# 001-H-01_CAN_to_Bluetooth.net
KiCad netlist of a schematic drawn in Altium Designer
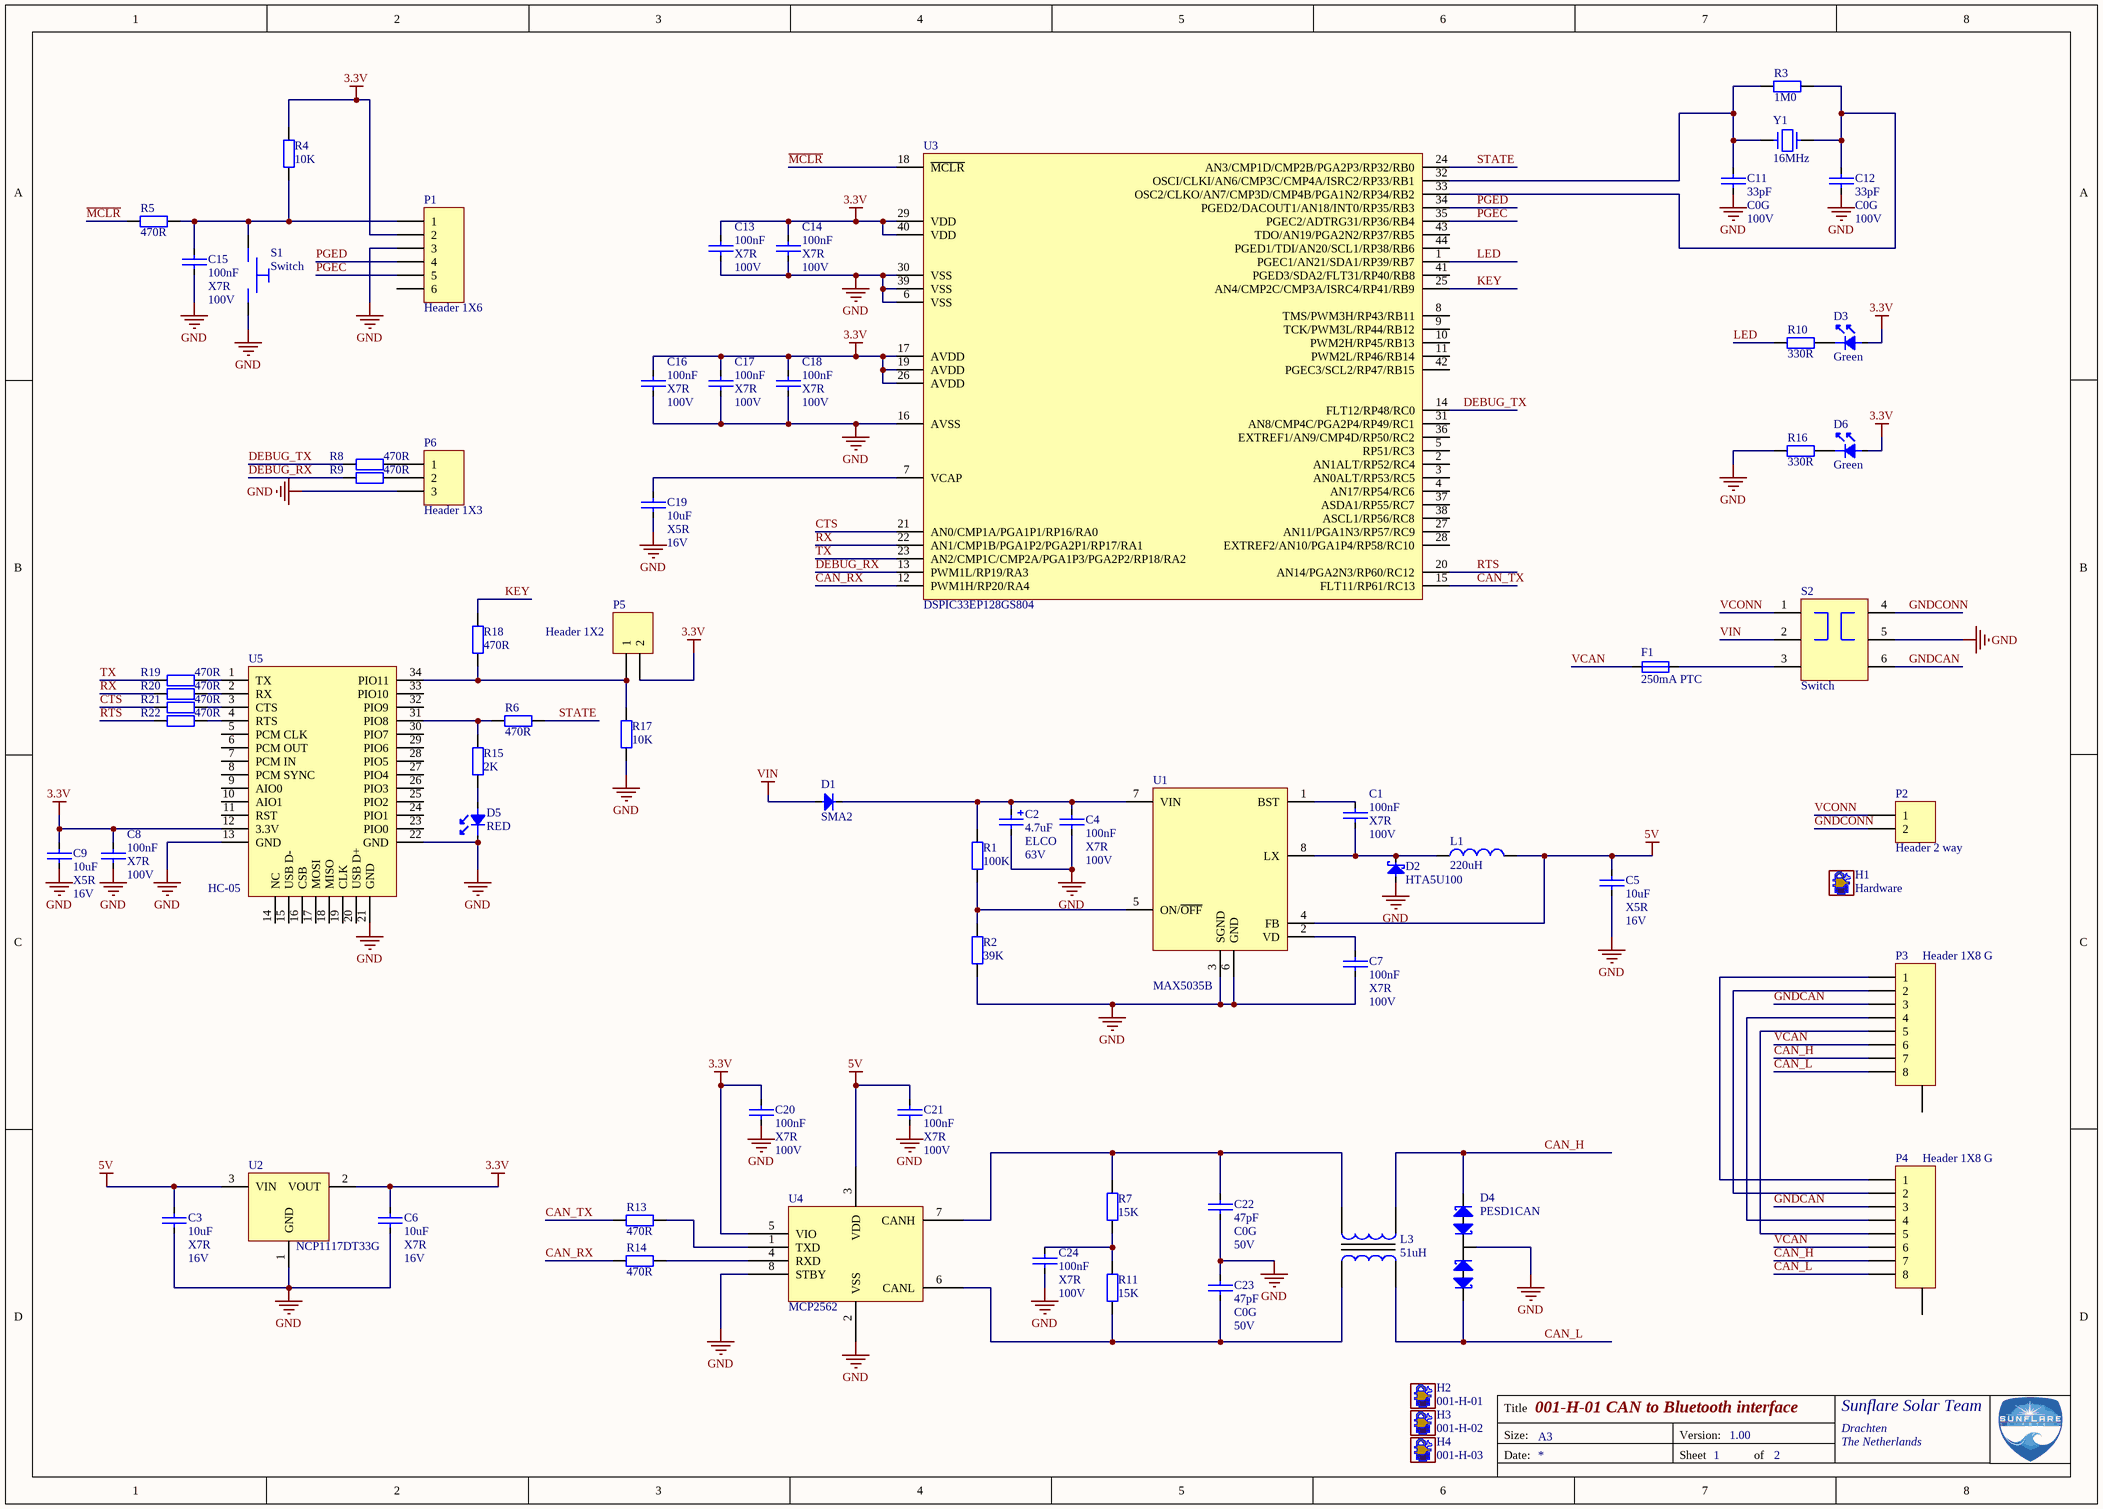
[diagram p0: 001-H-01 CAN to Bluetooth.SchDoc]

(export (version "E")
  (design (tool "Eeschema 10.0.6"))
  (components
    (comp (ref "C1")
      (value "100nF")
      (footprint "CAP0805")
      (description "Capacitor")
      (fields (field (name "DIELECTRIC") "X7R") (field (name "VOLTAGERATING") "100V"))
      (libsource (lib "001-H-01 CAN to Bluetooth") (part "Capacitor"))
    )
    (comp (ref "C2")
      (value "4.7uF")
      (footprint "CAPPOL5MM")
      (description "Capacitor Pol")
      (fields
        (field (name "MANUFACTURER") "WURTH ELEKTRONIK")
        (field (name "MANUFACTURER PART NO") "865060742001")
        (field (name "DIELECTRIC") "ELCO")
        (field (name "VOLTAGERATING") "63V")
      )
      (libsource (lib "001-H-01 CAN to Bluetooth") (part "CapacitorPol"))
    )
    (comp (ref "C3")
      (value "10uF")
      (footprint "CAP1210")
      (description "Capacitor")
      (fields
        (field (name "MANUFACTURER") "TDK")
        (field (name "MANUFACTURER PART NO") "C3225X7R1C106K200AB")
        (field (name "DIELECTRIC") "X7R")
        (field (name "VOLTAGERATING") "16V")
      )
      (libsource (lib "001-H-01 CAN to Bluetooth") (part "Capacitor"))
    )
    (comp (ref "C4")
      (value "100nF")
      (footprint "CAP0805")
      (description "Capacitor")
      (fields (field (name "DIELECTRIC") "X7R") (field (name "VOLTAGERATING") "100V"))
      (libsource (lib "001-H-01 CAN to Bluetooth") (part "Capacitor"))
    )
    (comp (ref "C5")
      (value "10uF")
      (footprint "CAP1210")
      (description "Capacitor")
      (fields
        (field (name "MANUFACTURER") "Multicomp")
        (field (name "MANUFACTURER PART NO") "MC1210X106K160CT")
        (field (name "DIELECTRIC") "X5R")
        (field (name "VOLTAGERATING") "16V")
      )
      (libsource (lib "001-H-01 CAN to Bluetooth") (part "Capacitor"))
    )
    (comp (ref "C6")
      (value "10uF")
      (footprint "CAP1210")
      (description "Capacitor")
      (fields
        (field (name "MANUFACTURER") "TDK")
        (field (name "MANUFACTURER PART NO") "C3225X7R1C106K200AB")
        (field (name "DIELECTRIC") "X7R")
        (field (name "VOLTAGERATING") "16V")
      )
      (libsource (lib "001-H-01 CAN to Bluetooth") (part "Capacitor"))
    )
    (comp (ref "C7")
      (value "100nF")
      (footprint "CAP0805")
      (description "Capacitor")
      (fields (field (name "DIELECTRIC") "X7R") (field (name "VOLTAGERATING") "100V"))
      (libsource (lib "001-H-01 CAN to Bluetooth") (part "Capacitor"))
    )
    (comp (ref "C8")
      (value "100nF")
      (footprint "CAP0805")
      (description "Capacitor")
      (fields (field (name "DIELECTRIC") "X7R") (field (name "VOLTAGERATING") "100V"))
      (libsource (lib "001-H-01 CAN to Bluetooth") (part "Capacitor"))
    )
    (comp (ref "C9")
      (value "10uF")
      (footprint "CAP1210")
      (description "Capacitor")
      (fields
        (field (name "MANUFACTURER") "Multicomp")
        (field (name "MANUFACTURER PART NO") "MC1210X106K160CT")
        (field (name "DIELECTRIC") "X5R")
        (field (name "VOLTAGERATING") "16V")
      )
      (libsource (lib "001-H-01 CAN to Bluetooth") (part "Capacitor"))
    )
    (comp (ref "C11")
      (value "33pF")
      (footprint "CAP0805")
      (description "Capacitor")
      (fields (field (name "DIELECTRIC") "C0G") (field (name "VOLTAGERATING") "100V"))
      (libsource (lib "001-H-01 CAN to Bluetooth") (part "Capacitor"))
    )
    (comp (ref "C12")
      (value "33pF")
      (footprint "CAP0805")
      (description "Capacitor")
      (fields (field (name "DIELECTRIC") "C0G") (field (name "VOLTAGERATING") "100V"))
      (libsource (lib "001-H-01 CAN to Bluetooth") (part "Capacitor"))
    )
    (comp (ref "C13")
      (value "100nF")
      (footprint "CAP0805")
      (description "Capacitor")
      (fields (field (name "DIELECTRIC") "X7R") (field (name "VOLTAGERATING") "100V"))
      (libsource (lib "001-H-01 CAN to Bluetooth") (part "Capacitor"))
    )
    (comp (ref "C14")
      (value "100nF")
      (footprint "CAP0805")
      (description "Capacitor")
      (fields (field (name "DIELECTRIC") "X7R") (field (name "VOLTAGERATING") "100V"))
      (libsource (lib "001-H-01 CAN to Bluetooth") (part "Capacitor"))
    )
    (comp (ref "C15")
      (value "100nF")
      (footprint "CAP0805")
      (description "Capacitor")
      (fields (field (name "DIELECTRIC") "X7R") (field (name "VOLTAGERATING") "100V"))
      (libsource (lib "001-H-01 CAN to Bluetooth") (part "Capacitor"))
    )
    (comp (ref "C16")
      (value "100nF")
      (footprint "CAP0805")
      (description "Capacitor")
      (fields (field (name "DIELECTRIC") "X7R") (field (name "VOLTAGERATING") "100V"))
      (libsource (lib "001-H-01 CAN to Bluetooth") (part "Capacitor"))
    )
    (comp (ref "C17")
      (value "100nF")
      (footprint "CAP0805")
      (description "Capacitor")
      (fields (field (name "DIELECTRIC") "X7R") (field (name "VOLTAGERATING") "100V"))
      (libsource (lib "001-H-01 CAN to Bluetooth") (part "Capacitor"))
    )
    (comp (ref "C18")
      (value "100nF")
      (footprint "CAP0805")
      (description "Capacitor")
      (fields (field (name "DIELECTRIC") "X7R") (field (name "VOLTAGERATING") "100V"))
      (libsource (lib "001-H-01 CAN to Bluetooth") (part "Capacitor"))
    )
    (comp (ref "C19")
      (value "10uF")
      (footprint "CAP1210")
      (description "Capacitor")
      (fields
        (field (name "MANUFACTURER") "Multicomp")
        (field (name "MANUFACTURER PART NO") "MC1210X106K160CT")
        (field (name "DIELECTRIC") "X5R")
        (field (name "VOLTAGERATING") "16V")
      )
      (libsource (lib "001-H-01 CAN to Bluetooth") (part "Capacitor"))
    )
    (comp (ref "C20")
      (value "100nF")
      (footprint "CAP0805")
      (description "Capacitor")
      (fields (field (name "DIELECTRIC") "X7R") (field (name "VOLTAGERATING") "100V"))
      (libsource (lib "001-H-01 CAN to Bluetooth") (part "Capacitor"))
    )
    (comp (ref "C21")
      (value "100nF")
      (footprint "CAP0805")
      (description "Capacitor")
      (fields (field (name "DIELECTRIC") "X7R") (field (name "VOLTAGERATING") "100V"))
      (libsource (lib "001-H-01 CAN to Bluetooth") (part "Capacitor"))
    )
    (comp (ref "C22")
      (value "47pF")
      (footprint "CAP0805")
      (description "Capacitor")
      (fields (field (name "DIELECTRIC") "C0G") (field (name "VOLTAGERATING") "50V"))
      (libsource (lib "001-H-01 CAN to Bluetooth") (part "Capacitor"))
    )
    (comp (ref "C23")
      (value "47pF")
      (footprint "CAP0805")
      (description "Capacitor")
      (fields (field (name "DIELECTRIC") "C0G") (field (name "VOLTAGERATING") "50V"))
      (libsource (lib "001-H-01 CAN to Bluetooth") (part "Capacitor"))
    )
    (comp (ref "C24")
      (value "100nF")
      (footprint "CAP0805")
      (description "Capacitor")
      (fields (field (name "DIELECTRIC") "X7R") (field (name "VOLTAGERATING") "100V"))
      (libsource (lib "001-H-01 CAN to Bluetooth") (part "Capacitor"))
    )
    (comp (ref "D1")
      (value "SMA2")
      (footprint "DIODEDO-214AC")
      (description "Diode")
      (fields (field (name "MANUFACTURER") "Multicomp") (field (name "MANUFACTURER PART NO") "S2MA"))
      (libsource (lib "001-H-01 CAN to Bluetooth") (part "Diode"))
    )
    (comp (ref "D2")
      (value "HTA5U100")
      (footprint "DIODEDO-214AC")
      (description "Diode Schottky")
      (fields (field (name "MANUFACTURER") "Multicomp"))
      (libsource (lib "001-H-01 CAN to Bluetooth") (part "Diode Schottky"))
    )
    (comp (ref "D3")
      (value "Green")
      (footprint "LEDTHT")
      (description "Led")
      (fields (field (name "MANUFACTURER") "Multicomp") (field (name "MANUFACTURER PART NO") "MCL034GT"))
      (libsource (lib "001-H-01 CAN to Bluetooth") (part "Led"))
    )
    (comp (ref "D4")
      (value "PESD1CAN")
      (footprint "SOT23-3N")
      (description "ESD Protection Device, TVS, 70 V, SOT-23, 3 Pins")
      (fields (field (name "MANUFACTURER") "NXP"))
      (libsource (lib "001-H-01 CAN to Bluetooth") (part "PESD1CAN"))
    )
    (comp (ref "D5")
      (value "RED")
      (footprint "LEDTHT")
      (description "Led")
      (fields (field (name "MANUFACTURER") "Multicomp") (field (name "MANUFACTURER PART NO") "MCL034PT"))
      (libsource (lib "001-H-01 CAN to Bluetooth") (part "Led"))
    )
    (comp (ref "D6")
      (value "Green")
      (footprint "LEDTHT")
      (description "Led")
      (fields (field (name "MANUFACTURER") "Multicomp") (field (name "MANUFACTURER PART NO") "MCL034GT"))
      (libsource (lib "001-H-01 CAN to Bluetooth") (part "Led"))
    )
    (comp (ref "F1")
      (value "250mA PTC")
      (footprint "Fuse 1206")
      (description "Fuse")
      (fields
        (field (name "MANUFACTURER") "EATON BUSSMANN SERIES")
        (field (name "MANUFACTURER PART NO") "PTS120660V010")
      )
      (libsource (lib "001-H-01 CAN to Bluetooth") (part "Fuse"))
    )
    (comp (ref "H1")
      (value "Hardware")
      (description "Generaric hardware")
      (fields
        (field (name "MANUFACTURER") "IMO PRECISION CONTROLS")
        (field (name "MANUFACTURER PART NO") "21.950M/2-E")
      )
      (libsource (lib "001-H-01 CAN to Bluetooth") (part "Hardware"))
    )
    (comp (ref "H2")
      (value "001-H-01")
      (description "PCB")
      (libsource (lib "001-H-01 CAN to Bluetooth") (part "Hardware"))
    )
    (comp (ref "H3")
      (value "001-H-02")
      (description "Casing bottom")
      (libsource (lib "001-H-01 CAN to Bluetooth") (part "Hardware"))
    )
    (comp (ref "H4")
      (value "001-H-03")
      (description "Casing top")
      (libsource (lib "001-H-01 CAN to Bluetooth") (part "Hardware"))
    )
    (comp (ref "L1")
      (value "220uH")
      (footprint "INDWE-PD")
      (description "Inductor")
      (fields (field (name "MANUFACTURER") "WE") (field (name "MANUFACTURER PART NO") "744777222"))
      (libsource (lib "001-H-01 CAN to Bluetooth") (part "Inductor"))
    )
    (comp (ref "L3")
      (value "51uH")
      (footprint "IND200P450X300-4N")
      (description "Choke common mode")
      (fields (field (name "MANUFACTURER") "Bourns") (field (name "MANUFACTURER PART NO") "SRF4532-510Y"))
      (libsource (lib "001-H-01 CAN to Bluetooth") (part "Choke Common Mode"))
    )
    (comp (ref "P1")
      (value "Header 1X6")
      (footprint "Header1X6P100_Program")
      (description "Connector 1X6")
      (libsource (lib "001-H-01 CAN to Bluetooth") (part "Header1X6"))
    )
    (comp (ref "P2")
      (value "Header 2 way")
      (footprint "21.95MH/2-E")
      (fields
        (field (name "MANUFACTURER") "IMO PRECISION CONTROLS")
        (field (name "MANUFACTURER PART NO") "21.95MH/2-E")
      )
      (libsource (lib "") (part "Header1X2_1"))
    )
    (comp (ref "P3")
      (value "Header 1X8 G")
      (footprint "TECO-1-406541-5")
      (description "Connector 1X8 with Ground")
      (libsource (lib "001-H-01 CAN to Bluetooth") (part "Header1X8+G"))
    )
    (comp (ref "P4")
      (value "Header 1X8 G")
      (footprint "TECO-1-406541-5")
      (description "Connector 1X8 with Ground")
      (libsource (lib "001-H-01 CAN to Bluetooth") (part "Header1X8+G"))
    )
    (comp (ref "P5")
      (value "Header 1X2")
      (footprint "Header1X2P100")
      (description "Connector 1X2")
      (libsource (lib "001-H-01 CAN to Bluetooth") (part "Header1X2"))
    )
    (comp (ref "P6")
      (value "Header 1X3")
      (footprint "Header1X3P100")
      (description "Connector 1X3")
      (libsource (lib "001-H-01 CAN to Bluetooth") (part "Header1X3"))
    )
    (comp (ref "R1")
      (value "100K")
      (footprint "RES0603")
      (description "Resistor")
      (fields (field (name "TOLERANCE") "1%"))
      (libsource (lib "") (part "Resistor_2"))
    )
    (comp (ref "R2")
      (value "39K")
      (footprint "RES0603")
      (description "Resistor")
      (fields (field (name "TOLERANCE") "1%"))
      (libsource (lib "") (part "Resistor_2"))
    )
    (comp (ref "R3")
      (value "1M0")
      (footprint "RES0603")
      (description "Resistor")
      (fields (field (name "TOLERANCE") "1%"))
      (libsource (lib "") (part "Resistor_1"))
    )
    (comp (ref "R4")
      (value "10K")
      (footprint "RES0603")
      (description "Resistor")
      (fields (field (name "TOLERANCE") "1%"))
      (libsource (lib "") (part "Resistor_2"))
    )
    (comp (ref "R5")
      (value "470R")
      (footprint "RES0603")
      (description "Resistor")
      (fields (field (name "TOLERANCE") "1%"))
      (libsource (lib "") (part "Resistor_1"))
    )
    (comp (ref "R6")
      (value "470R")
      (footprint "RES0603")
      (description "Resistor")
      (fields (field (name "TOLERANCE") "1%"))
      (libsource (lib "") (part "Resistor_1"))
    )
    (comp (ref "R7")
      (value "15K")
      (footprint "RES0603")
      (description "Resistor")
      (fields (field (name "TOLERANCE") "1%"))
      (libsource (lib "") (part "Resistor_2"))
    )
    (comp (ref "R8")
      (value "470R")
      (footprint "RES0603")
      (description "Resistor")
      (fields (field (name "TOLERANCE") "1%"))
      (libsource (lib "") (part "Resistor_1"))
    )
    (comp (ref "R9")
      (value "470R")
      (footprint "RES0603")
      (description "Resistor")
      (fields (field (name "TOLERANCE") "1%"))
      (libsource (lib "") (part "Resistor_1"))
    )
    (comp (ref "R10")
      (value "330R")
      (footprint "RES0603")
      (description "Resistor")
      (fields (field (name "TOLERANCE") "1%"))
      (libsource (lib "") (part "Resistor_1"))
    )
    (comp (ref "R11")
      (value "15K")
      (footprint "RES0603")
      (description "Resistor")
      (fields (field (name "TOLERANCE") "1%"))
      (libsource (lib "") (part "Resistor_2"))
    )
    (comp (ref "R13")
      (value "470R")
      (footprint "RES0603")
      (description "Resistor")
      (fields (field (name "TOLERANCE") "1%"))
      (libsource (lib "") (part "Resistor_1"))
    )
    (comp (ref "R14")
      (value "470R")
      (footprint "RES0603")
      (description "Resistor")
      (fields (field (name "TOLERANCE") "1%"))
      (libsource (lib "") (part "Resistor_1"))
    )
    (comp (ref "R15")
      (value "2K")
      (footprint "RES0603")
      (description "Resistor")
      (fields (field (name "TOLERANCE") "1%"))
      (libsource (lib "") (part "Resistor_2"))
    )
    (comp (ref "R16")
      (value "330R")
      (footprint "RES0603")
      (description "Resistor")
      (fields (field (name "TOLERANCE") "1%"))
      (libsource (lib "") (part "Resistor_1"))
    )
    (comp (ref "R17")
      (value "10K")
      (footprint "RES0603")
      (description "Resistor")
      (fields (field (name "TOLERANCE") "1%"))
      (libsource (lib "001-H-01 CAN to Bluetooth") (part "Resistor"))
    )
    (comp (ref "R18")
      (value "470R")
      (footprint "RES0603")
      (description "Resistor")
      (fields (field (name "TOLERANCE") "1%"))
      (libsource (lib "001-H-01 CAN to Bluetooth") (part "Resistor"))
    )
    (comp (ref "R19")
      (value "470R")
      (footprint "RES0603")
      (description "Resistor")
      (fields (field (name "TOLERANCE") "1%"))
      (libsource (lib "") (part "Resistor_1"))
    )
    (comp (ref "R20")
      (value "470R")
      (footprint "RES0603")
      (description "Resistor")
      (fields (field (name "TOLERANCE") "1%"))
      (libsource (lib "") (part "Resistor_1"))
    )
    (comp (ref "R21")
      (value "470R")
      (footprint "RES0603")
      (description "Resistor")
      (fields (field (name "TOLERANCE") "1%"))
      (libsource (lib "") (part "Resistor_1"))
    )
    (comp (ref "R22")
      (value "470R")
      (footprint "RES0603")
      (description "Resistor")
      (fields (field (name "TOLERANCE") "1%"))
      (libsource (lib "") (part "Resistor_1"))
    )
    (comp (ref "S1")
      (value "Switch")
      (footprint "SWITCHTE1825027-2")
      (description "Tactile Switch")
      (fields
        (field (name "MANUFACTURER") "TE CONNECTIVITY")
        (field (name "MANUFACTURER PART NO") "FSMRA4JH")
      )
      (libsource (lib "001-H-01 CAN to Bluetooth") (part "TactileSwitch"))
    )
    (comp (ref "S2")
      (value "Switch")
      (footprint "JS202011AQN")
      (description "Tactile Switch")
      (fields
        (field (name "MANUFACTURER") "C&K COMPONENTS")
        (field (name "MANUFACTURER PART NO") "JS202011AQN")
      )
      (libsource (lib "001-H-01 CAN to Bluetooth") (part "DPDTSwitch"))
    )
    (comp (ref "U1")
      (value "MAX5035B")
      (footprint "SOIC-8N")
      (description "5V 1A, 76V, High-Efficiency MAXPower Step-Down DC-DC Converter")
      (fields
        (field (name "MANUFACTURER") "Maxim Integrated Products")
        (field (name "MANUFACTURER PART NO") "MAX5035BUSA+T")
      )
      (libsource (lib "001-H-01 CAN to Bluetooth") (part "MAX5035B"))
    )
    (comp (ref "U2")
      (value "NCP1117DT33G")
      (footprint "DPAK-3")
      (description "Fixed LDO Voltage Regulator, 20V in, 1.07V Dropout, 3.3V/1A out, DPAK-3")
      (fields (field (name "MANUFACTURER") "ON SEMICONDUCTOR"))
      (libsource (lib "001-H-01 CAN to Bluetooth") (part "NCP1117DT33G"))
    )
    (comp (ref "U3")
      (value "DSPIC33EP128GS804")
      (footprint "TQFP80P1200X1200X120-44N")
      (fields
        (field (name "MANUFACTURER") "Microchip")
        (field (name "MANUFACTURER PART NO") "DSPIC33EP128GS804-I/PT")
      )
      (libsource (lib "001-H-01 CAN to Bluetooth") (part "DSPIC33EP128GS804"))
    )
    (comp (ref "U4")
      (value "MCP2562")
      (footprint "SOIC-8N")
      (description "CAN Bus, Transceiver, CAN, LIN, 1, 1, 4.5 V, 5.5 V, SOIC")
      (fields (field (name "MANUFACTURER") "Microchip") (field (name "MANUFACTURER PART NO") "MCP2562-E/SN"))
      (libsource (lib "001-H-01 CAN to Bluetooth") (part "MCP2562"))
    )
    (comp (ref "U5")
      (value "HC-05")
      (footprint "HC-05")
      (description "Bluetooth Module")
      (libsource (lib "001-H-01 CAN to Bluetooth") (part "HC-05"))
    )
    (comp (ref "Y1")
      (value "16MHz")
      (footprint "XT49M-2016M")
      (description "Crystal")
      (fields
        (field (name "MANUFACTURER") "Multicomp")
        (field (name "MANUFACTURER PART NO") "MCRSD16000F183000RR")
      )
      (libsource (lib "001-H-01 CAN to Bluetooth") (part "Crystal"))
    )
  )
  (nets
    (net (code "1") (name "/CAN_H") (class "Default")
      (node (ref "D4") (pin "1") (pinfunction "1_1") (pintype "passive"))
      (node (ref "L3") (pin "2") (pinfunction "2_2") (pintype "passive"))
      (node (ref "P3") (pin "7") (pinfunction "7_7") (pintype "passive"))
      (node (ref "P4") (pin "7") (pinfunction "7_7") (pintype "passive"))
    )
    (net (code "2") (name "/CAN_L") (class "Default")
      (node (ref "D4") (pin "2") (pinfunction "2_2") (pintype "passive"))
      (node (ref "L3") (pin "3") (pinfunction "3_3") (pintype "passive"))
      (node (ref "P3") (pin "8") (pinfunction "8_8") (pintype "passive"))
      (node (ref "P4") (pin "8") (pinfunction "8_8") (pintype "passive"))
    )
    (net (code "3") (name "/CAN_RX") (class "Default")
      (node (ref "R14") (pin "1") (pinfunction "1_1") (pintype "passive"))
      (node (ref "U3") (pin "12") (pinfunction "PWM1H/RP20/RA4_12") (pintype "passive"))
    )
    (net (code "4") (name "/CAN_TX") (class "Default")
      (node (ref "R13") (pin "1") (pinfunction "1_1") (pintype "passive"))
      (node (ref "U3") (pin "15") (pinfunction "FLT11/RP61/RC13_15") (pintype "passive"))
    )
    (net (code "5") (name "/CTS") (class "Default")
      (node (ref "R21") (pin "1") (pinfunction "1_1") (pintype "passive"))
      (node (ref "U3") (pin "21") (pinfunction "AN0/CMP1A/PGA1P1/RP16/RA0_21") (pintype "passive"))
    )
    (net (code "6") (name "/DEBUG_RX") (class "Default")
      (node (ref "R9") (pin "1") (pinfunction "1_1") (pintype "passive"))
      (node (ref "U3") (pin "13") (pinfunction "PWM1L/RP19/RA3_13") (pintype "passive"))
    )
    (net (code "7") (name "/DEBUG_TX") (class "Default")
      (node (ref "R8") (pin "1") (pinfunction "1_1") (pintype "passive"))
      (node (ref "U3") (pin "14") (pinfunction "FLT12/RP48/RC0_14") (pintype "passive"))
    )
    (net (code "8") (name "/GNDCAN") (class "Default")
      (node (ref "P3") (pin "3") (pinfunction "3_3") (pintype "passive"))
      (node (ref "P4") (pin "3") (pinfunction "3_3") (pintype "passive"))
      (node (ref "S2") (pin "6") (pinfunction "6_6") (pintype "passive"))
    )
    (net (code "9") (name "/GNDCONN") (class "Default")
      (node (ref "P2") (pin "2") (pinfunction "2_2") (pintype "passive"))
      (node (ref "S2") (pin "4") (pinfunction "4_4") (pintype "passive"))
    )
    (net (code "10") (name "/KEY") (class "Default")
      (node (ref "R18") (pin "2") (pinfunction "2_2") (pintype "passive"))
      (node (ref "U3") (pin "25") (pinfunction "AN4/CMP2C/CMP3A/ISRC4/RP41/RB9_25") (pintype "passive"))
    )
    (net (code "11") (name "/LED") (class "Default")
      (node (ref "R10") (pin "1") (pinfunction "1_1") (pintype "passive"))
      (node (ref "U3") (pin "1") (pinfunction "PGEC1/AN21/SDA1/RP39/RB7_1") (pintype "passive"))
    )
    (net (code "12") (name "/PGEC") (class "Default")
      (node (ref "P1") (pin "5") (pinfunction "5_5") (pintype "passive"))
      (node (ref "U3") (pin "35") (pinfunction "PGEC2/ADTRG31/RP36/RB4_35") (pintype "passive"))
    )
    (net (code "13") (name "/PGED") (class "Default")
      (node (ref "P1") (pin "4") (pinfunction "4_4") (pintype "passive"))
      (node (ref "U3") (pin "34") (pinfunction "PGED2/DACOUT1/AN18/INT0/RP35/RB3_34") (pintype "passive"))
    )
    (net (code "14") (name "/RTS") (class "Default")
      (node (ref "R22") (pin "1") (pinfunction "1_1") (pintype "passive"))
      (node (ref "U3") (pin "20") (pinfunction "AN14/PGA2N3/RP60/RC12_20") (pintype "passive"))
    )
    (net (code "15") (name "/RX") (class "Default")
      (node (ref "R20") (pin "1") (pinfunction "1_1") (pintype "passive"))
      (node (ref "U3") (pin "22") (pinfunction "AN1/CMP1B/PGA1P2/PGA2P1/RP17/RA1_22") (pintype "passive"))
    )
    (net (code "16") (name "/STATE") (class "Default")
      (node (ref "R6") (pin "2") (pinfunction "2_2") (pintype "passive"))
      (node (ref "U3") (pin "24") (pinfunction "AN3/CMP1D/CMP2B/PGA2P3/RP32/RB0_24") (pintype "passive"))
    )
    (net (code "17") (name "/TX") (class "Default")
      (node (ref "R19") (pin "1") (pinfunction "1_1") (pintype "passive"))
      (node (ref "U3") (pin "23") (pinfunction "AN2/CMP1C/CMP2A/PGA1P3/PGA2P2/RP18/RA2_23") (pintype "passive"))
    )
    (net (code "18") (name "/VCAN") (class "Default")
      (node (ref "F1") (pin "1") (pinfunction "1_1") (pintype "passive"))
      (node (ref "P3") (pin "6") (pinfunction "6_6") (pintype "passive"))
      (node (ref "P4") (pin "6") (pinfunction "6_6") (pintype "passive"))
    )
    (net (code "19") (name "/VCONN") (class "Default")
      (node (ref "P2") (pin "1") (pinfunction "1_1") (pintype "passive"))
      (node (ref "S2") (pin "1") (pinfunction "1_1") (pintype "passive"))
    )
    (net (code "20") (name "/~{MCLR}") (class "Default")
      (node (ref "R5") (pin "1") (pinfunction "1_1") (pintype "passive"))
      (node (ref "U3") (pin "18") (pinfunction "~{MCLR}_18") (pintype "passive"))
    )
    (net (code "21") (name "3.3V") (class "Default")
      (node (ref "C13") (pin "2") (pinfunction "2_2") (pintype "passive"))
      (node (ref "C14") (pin "2") (pinfunction "2_2") (pintype "passive"))
      (node (ref "C16") (pin "2") (pinfunction "2_2") (pintype "passive"))
      (node (ref "C17") (pin "2") (pinfunction "2_2") (pintype "passive"))
      (node (ref "C18") (pin "2") (pinfunction "2_2") (pintype "passive"))
      (node (ref "C20") (pin "2") (pinfunction "2_2") (pintype "passive"))
      (node (ref "C6") (pin "2") (pinfunction "2_2") (pintype "passive"))
      (node (ref "C8") (pin "2") (pinfunction "2_2") (pintype "passive"))
      (node (ref "C9") (pin "2") (pinfunction "2_2") (pintype "passive"))
      (node (ref "D3") (pin "2") (pinfunction "A_2") (pintype "passive"))
      (node (ref "D6") (pin "2") (pinfunction "A_2") (pintype "passive"))
      (node (ref "P1") (pin "2") (pinfunction "2_2") (pintype "passive"))
      (node (ref "P5") (pin "2") (pinfunction "2_2") (pintype "passive"))
      (node (ref "R4") (pin "1") (pinfunction "1_1") (pintype "passive"))
      (node (ref "U2") (pin "2") (pinfunction "VOUT_2") (pintype "passive"))
      (node (ref "U3") (pin "17") (pinfunction "AVDD_17") (pintype "passive"))
      (node (ref "U3") (pin "19") (pinfunction "AVDD_19") (pintype "passive"))
      (node (ref "U3") (pin "26") (pinfunction "AVDD_26") (pintype "passive"))
      (node (ref "U3") (pin "29") (pinfunction "VDD_29") (pintype "passive"))
      (node (ref "U3") (pin "40") (pinfunction "VDD_40") (pintype "passive"))
      (node (ref "U4") (pin "5") (pinfunction "VIO_5") (pintype "passive"))
      (node (ref "U5") (pin "12") (pinfunction "3.3V_12") (pintype "passive"))
    )
    (net (code "22") (name "5V") (class "Default")
      (node (ref "C21") (pin "2") (pinfunction "2_2") (pintype "passive"))
      (node (ref "C3") (pin "2") (pinfunction "2_2") (pintype "passive"))
      (node (ref "C5") (pin "2") (pinfunction "2_2") (pintype "passive"))
      (node (ref "L1") (pin "2") (pinfunction "2_2") (pintype "passive"))
      (node (ref "U1") (pin "4") (pinfunction "FB_4") (pintype "passive"))
      (node (ref "U2") (pin "3") (pinfunction "VIN_3") (pintype "passive"))
      (node (ref "U4") (pin "3") (pinfunction "VDD_3") (pintype "passive"))
    )
    (net (code "23") (name "GND") (class "Default")
      (node (ref "C11") (pin "1") (pinfunction "1_1") (pintype "passive"))
      (node (ref "C12") (pin "1") (pinfunction "1_1") (pintype "passive"))
      (node (ref "C13") (pin "1") (pinfunction "1_1") (pintype "passive"))
      (node (ref "C14") (pin "1") (pinfunction "1_1") (pintype "passive"))
      (node (ref "C15") (pin "2") (pinfunction "2_2") (pintype "passive"))
      (node (ref "C16") (pin "1") (pinfunction "1_1") (pintype "passive"))
      (node (ref "C17") (pin "1") (pinfunction "1_1") (pintype "passive"))
      (node (ref "C18") (pin "1") (pinfunction "1_1") (pintype "passive"))
      (node (ref "C19") (pin "1") (pinfunction "1_1") (pintype "passive"))
      (node (ref "C2") (pin "2") (pinfunction "2_2") (pintype "passive"))
      (node (ref "C20") (pin "1") (pinfunction "1_1") (pintype "passive"))
      (node (ref "C21") (pin "1") (pinfunction "1_1") (pintype "passive"))
      (node (ref "C22") (pin "1") (pinfunction "1_1") (pintype "passive"))
      (node (ref "C23") (pin "2") (pinfunction "2_2") (pintype "passive"))
      (node (ref "C24") (pin "1") (pinfunction "1_1") (pintype "passive"))
      (node (ref "C3") (pin "1") (pinfunction "1_1") (pintype "passive"))
      (node (ref "C4") (pin "1") (pinfunction "1_1") (pintype "passive"))
      (node (ref "C5") (pin "1") (pinfunction "1_1") (pintype "passive"))
      (node (ref "C6") (pin "1") (pinfunction "1_1") (pintype "passive"))
      (node (ref "C7") (pin "1") (pinfunction "1_1") (pintype "passive"))
      (node (ref "C8") (pin "1") (pinfunction "1_1") (pintype "passive"))
      (node (ref "C9") (pin "1") (pinfunction "1_1") (pintype "passive"))
      (node (ref "D2") (pin "2") (pinfunction "A_2") (pintype "passive"))
      (node (ref "D4") (pin "3") (pinfunction "3_3") (pintype "passive"))
      (node (ref "D5") (pin "1") (pinfunction "K_1") (pintype "passive"))
      (node (ref "P1") (pin "3") (pinfunction "3_3") (pintype "passive"))
      (node (ref "P6") (pin "3") (pinfunction "3_3") (pintype "passive"))
      (node (ref "R16") (pin "1") (pinfunction "1_1") (pintype "passive"))
      (node (ref "R17") (pin "1") (pinfunction "1_1") (pintype "passive"))
      (node (ref "R2") (pin "2") (pinfunction "2_2") (pintype "passive"))
      (node (ref "S1") (pin "2") (pinfunction "2_2") (pintype "passive"))
      (node (ref "S2") (pin "5") (pinfunction "5_5") (pintype "passive"))
      (node (ref "U1") (pin "3") (pinfunction "SGND_3") (pintype "passive"))
      (node (ref "U1") (pin "6") (pinfunction "GND_6") (pintype "passive"))
      (node (ref "U2") (pin "1") (pinfunction "GND_1") (pintype "passive"))
      (node (ref "U3") (pin "16") (pinfunction "AVSS_16") (pintype "passive"))
      (node (ref "U3") (pin "30") (pinfunction "VSS_30") (pintype "passive"))
      (node (ref "U3") (pin "39") (pinfunction "VSS_39") (pintype "passive"))
      (node (ref "U3") (pin "6") (pinfunction "VSS_6") (pintype "passive"))
      (node (ref "U4") (pin "2") (pinfunction "VSS_2") (pintype "passive"))
      (node (ref "U4") (pin "8") (pinfunction "STBY_8") (pintype "passive"))
      (node (ref "U5") (pin "13") (pinfunction "GND_13") (pintype "passive"))
      (node (ref "U5") (pin "21") (pinfunction "GND_21") (pintype "passive"))
      (node (ref "U5") (pin "22") (pinfunction "GND_22") (pintype "passive"))
    )
    (net (code "24") (name "Net-(C15-Pad1)") (class "Default")
      (node (ref "C15") (pin "1") (pinfunction "1_1") (pintype "passive"))
      (node (ref "P1") (pin "1") (pinfunction "1_1") (pintype "passive"))
      (node (ref "R4") (pin "2") (pinfunction "2_2") (pintype "passive"))
      (node (ref "R5") (pin "2") (pinfunction "2_2") (pintype "passive"))
      (node (ref "S1") (pin "1") (pinfunction "1_1") (pintype "passive"))
    )
    (net (code "25") (name "Net-(C24-Pad2)") (class "Default")
      (node (ref "C24") (pin "2") (pinfunction "2_2") (pintype "passive"))
      (node (ref "R11") (pin "1") (pinfunction "1_1") (pintype "passive"))
      (node (ref "R7") (pin "2") (pinfunction "2_2") (pintype "passive"))
    )
    (net (code "26") (name "Net-(D1-K)") (class "Default")
      (node (ref "C2") (pin "1") (pinfunction "1_1") (pintype "passive"))
      (node (ref "C4") (pin "2") (pinfunction "2_2") (pintype "passive"))
      (node (ref "D1") (pin "1") (pinfunction "K_1") (pintype "passive"))
      (node (ref "R1") (pin "1") (pinfunction "1_1") (pintype "passive"))
      (node (ref "U1") (pin "7") (pinfunction "VIN_7") (pintype "passive"))
    )
    (net (code "27") (name "Net-(D2-K)") (class "Default")
      (node (ref "C1") (pin "1") (pinfunction "1_1") (pintype "passive"))
      (node (ref "D2") (pin "1") (pinfunction "K_1") (pintype "passive"))
      (node (ref "L1") (pin "1") (pinfunction "1_1") (pintype "passive"))
      (node (ref "U1") (pin "8") (pinfunction "LX_8") (pintype "passive"))
    )
    (net (code "28") (name "Net-(D3-K)") (class "Default")
      (node (ref "D3") (pin "1") (pinfunction "K_1") (pintype "passive"))
      (node (ref "R10") (pin "2") (pinfunction "2_2") (pintype "passive"))
    )
    (net (code "29") (name "Net-(D5-A)") (class "Default")
      (node (ref "D5") (pin "2") (pinfunction "A_2") (pintype "passive"))
      (node (ref "R15") (pin "2") (pinfunction "2_2") (pintype "passive"))
    )
    (net (code "30") (name "Net-(D6-K)") (class "Default")
      (node (ref "D6") (pin "1") (pinfunction "K_1") (pintype "passive"))
      (node (ref "R16") (pin "2") (pinfunction "2_2") (pintype "passive"))
    )
    (net (code "31") (name "Net-(F1-Pad2)") (class "Default")
      (node (ref "F1") (pin "2") (pinfunction "2_2") (pintype "passive"))
      (node (ref "S2") (pin "3") (pinfunction "3_3") (pintype "passive"))
    )
    (net (code "32") (name "Net-(P3-Pad1)") (class "Default")
      (node (ref "P3") (pin "1") (pinfunction "1_1") (pintype "passive"))
      (node (ref "P4") (pin "1") (pinfunction "1_1") (pintype "passive"))
    )
    (net (code "33") (name "Net-(P3-Pad2)") (class "Default")
      (node (ref "P3") (pin "2") (pinfunction "2_2") (pintype "passive"))
      (node (ref "P4") (pin "2") (pinfunction "2_2") (pintype "passive"))
    )
    (net (code "34") (name "Net-(P3-Pad4)") (class "Default")
      (node (ref "P3") (pin "4") (pinfunction "4_4") (pintype "passive"))
      (node (ref "P4") (pin "4") (pinfunction "4_4") (pintype "passive"))
    )
    (net (code "35") (name "Net-(P3-Pad5)") (class "Default")
      (node (ref "P3") (pin "5") (pinfunction "5_5") (pintype "passive"))
      (node (ref "P4") (pin "5") (pinfunction "5_5") (pintype "passive"))
    )
    (net (code "36") (name "Net-(P6-Pad1)") (class "Default")
      (node (ref "P6") (pin "1") (pinfunction "1_1") (pintype "passive"))
      (node (ref "R8") (pin "2") (pinfunction "2_2") (pintype "passive"))
    )
    (net (code "37") (name "Net-(P6-Pad2)") (class "Default")
      (node (ref "P6") (pin "2") (pinfunction "2_2") (pintype "passive"))
      (node (ref "R9") (pin "2") (pinfunction "2_2") (pintype "passive"))
    )
    (net (code "38") (name "Net-(U1-BST)") (class "Default")
      (node (ref "C1") (pin "2") (pinfunction "2_2") (pintype "passive"))
      (node (ref "U1") (pin "1") (pinfunction "BST_1") (pintype "passive"))
    )
    (net (code "39") (name "Net-(U1-ON{slash}~{OFF})") (class "Default")
      (node (ref "R1") (pin "2") (pinfunction "2_2") (pintype "passive"))
      (node (ref "R2") (pin "1") (pinfunction "1_1") (pintype "passive"))
      (node (ref "U1") (pin "5") (pinfunction "ON/~{OFF}_5") (pintype "passive"))
    )
    (net (code "40") (name "Net-(U1-VD)") (class "Default")
      (node (ref "C7") (pin "2") (pinfunction "2_2") (pintype "passive"))
      (node (ref "U1") (pin "2") (pinfunction "VD_2") (pintype "passive"))
    )
    (net (code "41") (name "Net-(U3-OSC2{slash}CLKO{slash}AN7{slash}CMP3D{slash}CMP4B{slash}PGA1N2{slash}RP34{slash}RB2)") (class "Default")
      (node (ref "C12") (pin "2") (pinfunction "2_2") (pintype "passive"))
      (node (ref "R3") (pin "2") (pinfunction "2_2") (pintype "passive"))
      (node (ref "U3") (pin "33") (pinfunction "OSC2/CLKO/AN7/CMP3D/CMP4B/PGA1N2/RP34/RB2_33") (pintype "passive"))
      (node (ref "Y1") (pin "2") (pinfunction "2_2") (pintype "passive"))
    )
    (net (code "42") (name "Net-(U3-OSCI{slash}CLKI{slash}AN6{slash}CMP3C{slash}CMP4A{slash}ISRC2{slash}RP33{slash}RB1)") (class "Default")
      (node (ref "C11") (pin "2") (pinfunction "2_2") (pintype "passive"))
      (node (ref "R3") (pin "1") (pinfunction "1_1") (pintype "passive"))
      (node (ref "U3") (pin "32") (pinfunction "OSCI/CLKI/AN6/CMP3C/CMP4A/ISRC2/RP33/RB1_32") (pintype "passive"))
      (node (ref "Y1") (pin "1") (pinfunction "1_1") (pintype "passive"))
    )
    (net (code "43") (name "Net-(U3-VCAP)") (class "Default")
      (node (ref "C19") (pin "2") (pinfunction "2_2") (pintype "passive"))
      (node (ref "U3") (pin "7") (pinfunction "VCAP_7") (pintype "passive"))
    )
    (net (code "44") (name "Net-(U4-CANH)") (class "Default")
      (node (ref "C22") (pin "2") (pinfunction "2_2") (pintype "passive"))
      (node (ref "L3") (pin "1") (pinfunction "1_1") (pintype "passive"))
      (node (ref "R7") (pin "1") (pinfunction "1_1") (pintype "passive"))
      (node (ref "U4") (pin "7") (pinfunction "CANH_7") (pintype "passive"))
    )
    (net (code "45") (name "Net-(U4-CANL)") (class "Default")
      (node (ref "C23") (pin "1") (pinfunction "1_1") (pintype "passive"))
      (node (ref "L3") (pin "4") (pinfunction "4_4") (pintype "passive"))
      (node (ref "R11") (pin "2") (pinfunction "2_2") (pintype "passive"))
      (node (ref "U4") (pin "6") (pinfunction "CANL_6") (pintype "passive"))
    )
    (net (code "46") (name "Net-(U4-RXD)") (class "Default")
      (node (ref "R14") (pin "2") (pinfunction "2_2") (pintype "passive"))
      (node (ref "U4") (pin "4") (pinfunction "RXD_4") (pintype "passive"))
    )
    (net (code "47") (name "Net-(U4-TXD)") (class "Default")
      (node (ref "R13") (pin "2") (pinfunction "2_2") (pintype "passive"))
      (node (ref "U4") (pin "1") (pinfunction "TXD_1") (pintype "passive"))
    )
    (net (code "48") (name "Net-(U5-CTS)") (class "Default")
      (node (ref "R21") (pin "2") (pinfunction "2_2") (pintype "passive"))
      (node (ref "U5") (pin "3") (pinfunction "CTS_3") (pintype "passive"))
    )
    (net (code "49") (name "Net-(U5-PIO8)") (class "Default")
      (node (ref "R15") (pin "1") (pinfunction "1_1") (pintype "passive"))
      (node (ref "R6") (pin "1") (pinfunction "1_1") (pintype "passive"))
      (node (ref "U5") (pin "31") (pinfunction "PIO8_31") (pintype "passive"))
    )
    (net (code "50") (name "Net-(U5-PIO11)") (class "Default")
      (node (ref "P5") (pin "1") (pinfunction "1_1") (pintype "passive"))
      (node (ref "R17") (pin "2") (pinfunction "2_2") (pintype "passive"))
      (node (ref "R18") (pin "1") (pinfunction "1_1") (pintype "passive"))
      (node (ref "U5") (pin "34") (pinfunction "PIO11_34") (pintype "passive"))
    )
    (net (code "51") (name "Net-(U5-RTS)") (class "Default")
      (node (ref "R22") (pin "2") (pinfunction "2_2") (pintype "passive"))
      (node (ref "U5") (pin "4") (pinfunction "RTS_4") (pintype "passive"))
    )
    (net (code "52") (name "Net-(U5-RX)") (class "Default")
      (node (ref "R20") (pin "2") (pinfunction "2_2") (pintype "passive"))
      (node (ref "U5") (pin "2") (pinfunction "RX_2") (pintype "passive"))
    )
    (net (code "53") (name "Net-(U5-TX)") (class "Default")
      (node (ref "R19") (pin "2") (pinfunction "2_2") (pintype "passive"))
      (node (ref "U5") (pin "1") (pinfunction "TX_1") (pintype "passive"))
    )
    (net (code "54") (name "VIN") (class "Default")
      (node (ref "D1") (pin "2") (pinfunction "A_2") (pintype "passive"))
      (node (ref "S2") (pin "2") (pinfunction "2_2") (pintype "passive"))
    )
    (net (code "55") (name "unconnected-(P1-Pad6)") (class "Default")
      (node (ref "P1") (pin "6") (pinfunction "6_6") (pintype "passive"))
    )
    (net (code "56") (name "unconnected-(P3-G-Pad9)") (class "Default")
      (node (ref "P3") (pin "9") (pinfunction "G_9") (pintype "passive"))
    )
    (net (code "57") (name "unconnected-(P4-G-Pad9)") (class "Default")
      (node (ref "P4") (pin "9") (pinfunction "G_9") (pintype "passive"))
    )
    (net (code "58") (name "unconnected-(U3-AN0ALT{slash}RP53{slash}RC5-Pad3)") (class "Default")
      (node (ref "U3") (pin "3") (pinfunction "AN0ALT/RP53/RC5_3") (pintype "passive"))
    )
    (net (code "59") (name "unconnected-(U3-AN1ALT{slash}RP52{slash}RC4-Pad2)") (class "Default")
      (node (ref "U3") (pin "2") (pinfunction "AN1ALT/RP52/RC4_2") (pintype "passive"))
    )
    (net (code "60") (name "unconnected-(U3-AN8{slash}CMP4C{slash}PGA2P4{slash}RP49{slash}RC1-Pad31)") (class "Default")
      (node (ref "U3") (pin "31") (pinfunction "AN8/CMP4C/PGA2P4/RP49/RC1_31") (pintype "passive"))
    )
    (net (code "61") (name "unconnected-(U3-AN11{slash}PGA1N3{slash}RP57{slash}RC9-Pad27)") (class "Default")
      (node (ref "U3") (pin "27") (pinfunction "AN11/PGA1N3/RP57/RC9_27") (pintype "passive"))
    )
    (net (code "62") (name "unconnected-(U3-AN17{slash}RP54{slash}RC6-Pad4)") (class "Default")
      (node (ref "U3") (pin "4") (pinfunction "AN17/RP54/RC6_4") (pintype "passive"))
    )
    (net (code "63") (name "unconnected-(U3-ASCL1{slash}RP56{slash}RC8-Pad38)") (class "Default")
      (node (ref "U3") (pin "38") (pinfunction "ASCL1/RP56/RC8_38") (pintype "passive"))
    )
    (net (code "64") (name "unconnected-(U3-ASDA1{slash}RP55{slash}RC7-Pad37)") (class "Default")
      (node (ref "U3") (pin "37") (pinfunction "ASDA1/RP55/RC7_37") (pintype "passive"))
    )
    (net (code "65") (name "unconnected-(U3-EXTREF1{slash}AN9{slash}CMP4D{slash}RP50{slash}RC2-Pad36)") (class "Default")
      (node (ref "U3") (pin "36") (pinfunction "EXTREF1/AN9/CMP4D/RP50/RC2_36") (pintype "passive"))
    )
    (net (code "66") (name "unconnected-(U3-EXTREF2{slash}AN10{slash}PGA1P4{slash}RP58{slash}RC10-Pad28)") (class "Default")
      (node (ref "U3") (pin "28") (pinfunction "EXTREF2/AN10/PGA1P4/RP58/RC10_28") (pintype "passive"))
    )
    (net (code "67") (name "unconnected-(U3-PGEC3{slash}SCL2{slash}RP47{slash}RB15-Pad42)") (class "Default")
      (node (ref "U3") (pin "42") (pinfunction "PGEC3/SCL2/RP47/RB15_42") (pintype "passive"))
    )
    (net (code "68") (name "unconnected-(U3-PGED1{slash}TDI{slash}AN20{slash}SCL1{slash}RP38{slash}RB6-Pad44)") (class "Default")
      (node (ref "U3") (pin "44") (pinfunction "PGED1/TDI/AN20/SCL1/RP38/RB6_44") (pintype "passive"))
    )
    (net (code "69") (name "unconnected-(U3-PGED3{slash}SDA2{slash}FLT31{slash}RP40{slash}RB8-Pad41)") (class "Default")
      (node (ref "U3") (pin "41") (pinfunction "PGED3/SDA2/FLT31/RP40/RB8_41") (pintype "passive"))
    )
    (net (code "70") (name "unconnected-(U3-PWM2H{slash}RP45{slash}RB13-Pad10)") (class "Default")
      (node (ref "U3") (pin "10") (pinfunction "PWM2H/RP45/RB13_10") (pintype "passive"))
    )
    (net (code "71") (name "unconnected-(U3-PWM2L{slash}RP46{slash}RB14-Pad11)") (class "Default")
      (node (ref "U3") (pin "11") (pinfunction "PWM2L/RP46/RB14_11") (pintype "passive"))
    )
    (net (code "72") (name "unconnected-(U3-RP51{slash}RC3-Pad5)") (class "Default")
      (node (ref "U3") (pin "5") (pinfunction "RP51/RC3_5") (pintype "passive"))
    )
    (net (code "73") (name "unconnected-(U3-TCK{slash}PWM3L{slash}RP44{slash}RB12-Pad9)") (class "Default")
      (node (ref "U3") (pin "9") (pinfunction "TCK/PWM3L/RP44/RB12_9") (pintype "passive"))
    )
    (net (code "74") (name "unconnected-(U3-TDO{slash}AN19{slash}PGA2N2{slash}RP37{slash}RB5-Pad43)") (class "Default")
      (node (ref "U3") (pin "43") (pinfunction "TDO/AN19/PGA2N2/RP37/RB5_43") (pintype "passive"))
    )
    (net (code "75") (name "unconnected-(U3-TMS{slash}PWM3H{slash}RP43{slash}RB11-Pad8)") (class "Default")
      (node (ref "U3") (pin "8") (pinfunction "TMS/PWM3H/RP43/RB11_8") (pintype "passive"))
    )
    (net (code "76") (name "unconnected-(U5-AIO0-Pad9)") (class "Default")
      (node (ref "U5") (pin "9") (pinfunction "AIO0_9") (pintype "passive"))
    )
    (net (code "77") (name "unconnected-(U5-AIO1-Pad10)") (class "Default")
      (node (ref "U5") (pin "10") (pinfunction "AIO1_10") (pintype "passive"))
    )
    (net (code "78") (name "unconnected-(U5-CLK-Pad19)") (class "Default")
      (node (ref "U5") (pin "19") (pinfunction "CLK_19") (pintype "passive"))
    )
    (net (code "79") (name "unconnected-(U5-CSB-Pad16)") (class "Default")
      (node (ref "U5") (pin "16") (pinfunction "CSB_16") (pintype "passive"))
    )
    (net (code "80") (name "unconnected-(U5-MISO-Pad18)") (class "Default")
      (node (ref "U5") (pin "18") (pinfunction "MISO_18") (pintype "passive"))
    )
    (net (code "81") (name "unconnected-(U5-MOSI-Pad17)") (class "Default")
      (node (ref "U5") (pin "17") (pinfunction "MOSI_17") (pintype "passive"))
    )
    (net (code "82") (name "unconnected-(U5-NC-Pad14)") (class "Default")
      (node (ref "U5") (pin "14") (pinfunction "NC_14") (pintype "passive"))
    )
    (net (code "83") (name "unconnected-(U5-PCM_CLK-Pad5)") (class "Default")
      (node (ref "U5") (pin "5") (pinfunction "PCM_CLK_5") (pintype "passive"))
    )
    (net (code "84") (name "unconnected-(U5-PCM_IN-Pad7)") (class "Default")
      (node (ref "U5") (pin "7") (pinfunction "PCM_IN_7") (pintype "passive"))
    )
    (net (code "85") (name "unconnected-(U5-PCM_OUT-Pad6)") (class "Default")
      (node (ref "U5") (pin "6") (pinfunction "PCM_OUT_6") (pintype "passive"))
    )
    (net (code "86") (name "unconnected-(U5-PCM_SYNC-Pad8)") (class "Default")
      (node (ref "U5") (pin "8") (pinfunction "PCM_SYNC_8") (pintype "passive"))
    )
    (net (code "87") (name "unconnected-(U5-PIO0-Pad23)") (class "Default")
      (node (ref "U5") (pin "23") (pinfunction "PIO0_23") (pintype "passive"))
    )
    (net (code "88") (name "unconnected-(U5-PIO1-Pad24)") (class "Default")
      (node (ref "U5") (pin "24") (pinfunction "PIO1_24") (pintype "passive"))
    )
    (net (code "89") (name "unconnected-(U5-PIO2-Pad25)") (class "Default")
      (node (ref "U5") (pin "25") (pinfunction "PIO2_25") (pintype "passive"))
    )
    (net (code "90") (name "unconnected-(U5-PIO3-Pad26)") (class "Default")
      (node (ref "U5") (pin "26") (pinfunction "PIO3_26") (pintype "passive"))
    )
    (net (code "91") (name "unconnected-(U5-PIO4-Pad27)") (class "Default")
      (node (ref "U5") (pin "27") (pinfunction "PIO4_27") (pintype "passive"))
    )
    (net (code "92") (name "unconnected-(U5-PIO5-Pad28)") (class "Default")
      (node (ref "U5") (pin "28") (pinfunction "PIO5_28") (pintype "passive"))
    )
    (net (code "93") (name "unconnected-(U5-PIO6-Pad29)") (class "Default")
      (node (ref "U5") (pin "29") (pinfunction "PIO6_29") (pintype "passive"))
    )
    (net (code "94") (name "unconnected-(U5-PIO7-Pad30)") (class "Default")
      (node (ref "U5") (pin "30") (pinfunction "PIO7_30") (pintype "passive"))
    )
    (net (code "95") (name "unconnected-(U5-PIO9-Pad32)") (class "Default")
      (node (ref "U5") (pin "32") (pinfunction "PIO9_32") (pintype "passive"))
    )
    (net (code "96") (name "unconnected-(U5-PIO10-Pad33)") (class "Default")
      (node (ref "U5") (pin "33") (pinfunction "PIO10_33") (pintype "passive"))
    )
    (net (code "97") (name "unconnected-(U5-RST-Pad11)") (class "Default")
      (node (ref "U5") (pin "11") (pinfunction "RST_11") (pintype "passive"))
    )
    (net (code "98") (name "unconnected-(U5-USB_D+-Pad20)") (class "Default")
      (node (ref "U5") (pin "20") (pinfunction "USB_D+_20") (pintype "passive"))
    )
    (net (code "99") (name "unconnected-(U5-USB_D--Pad15)") (class "Default")
      (node (ref "U5") (pin "15") (pinfunction "USB_D-_15") (pintype "passive"))
    )
  )
)
